# PowerBoard.net
KiCad netlist of a schematic drawn in EAGLE
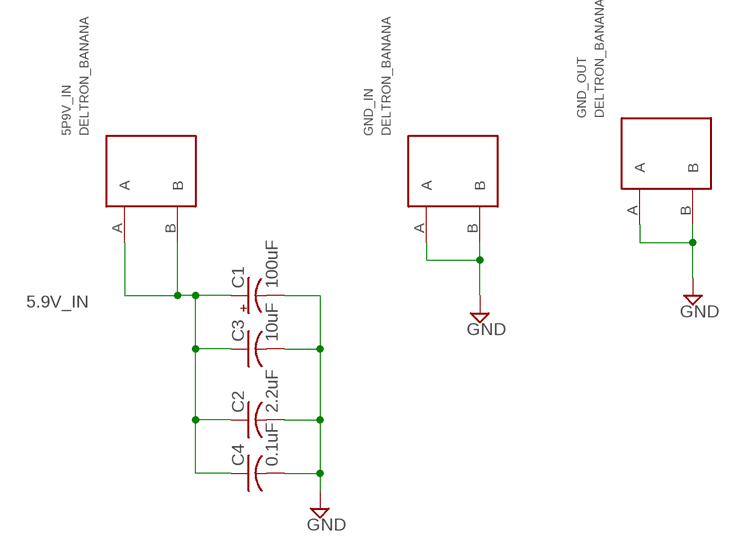
[diagram p0: schematic, sheet 1]
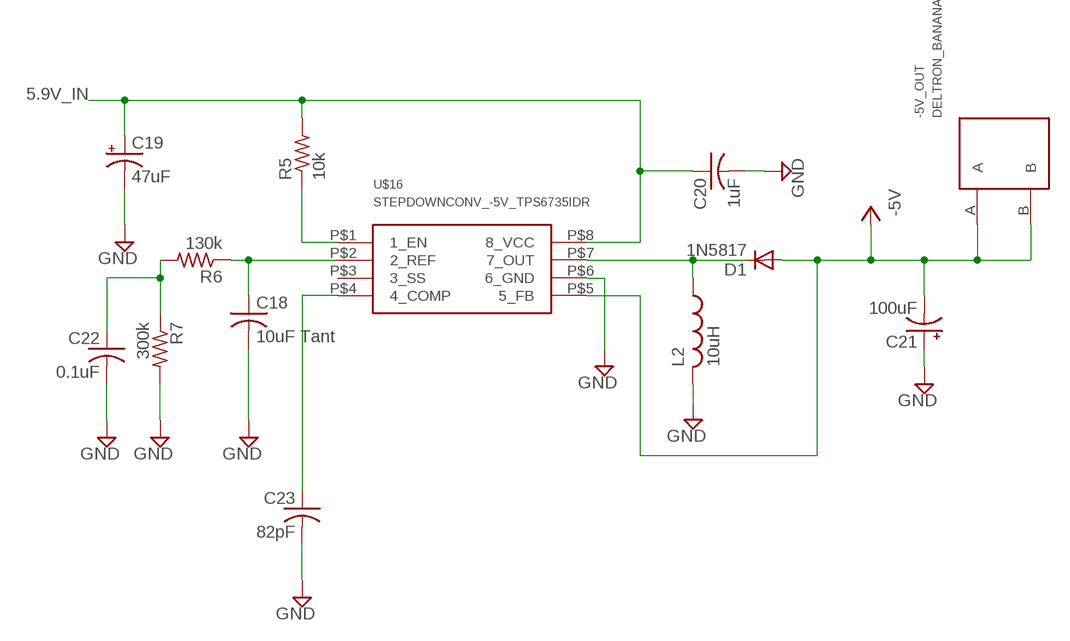
[diagram p1: schematic, sheet 2]
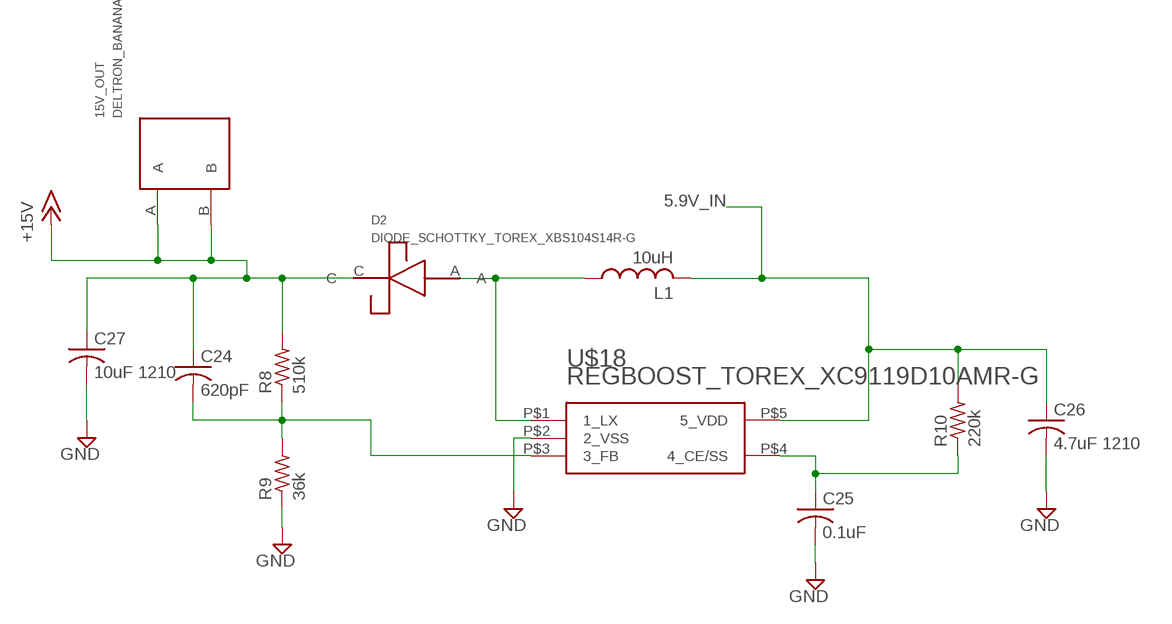
[diagram p2: schematic, sheet 3]
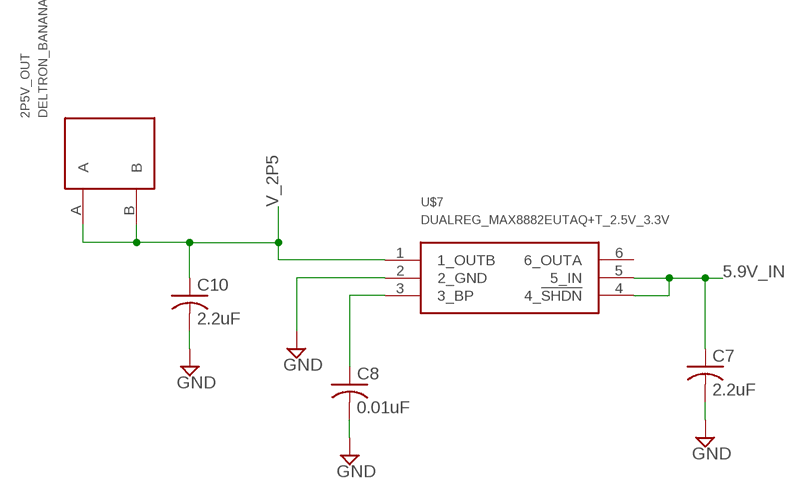
[diagram p3: schematic, sheet 4]

(export (version "E")
  (design (tool "Eeschema 10.0.6"))
  (components
    (comp (ref "15V_OUT")
      (value "DELTRON_BANANA")
      (footprint "eagle-import:DELTRON_BANANA")
      (libsource (lib "eagle-import") (part "DELTRON_BANANA"))
    )
    (comp (ref "C24")
      (value "620pF")
      (footprint "eagle-import:C0603")
      (libsource (lib "eagle-import") (part "C-USC0603"))
    )
    (comp (ref "C25")
      (value "0.1uF")
      (footprint "eagle-import:C0603")
      (libsource (lib "eagle-import") (part "C-USC0603"))
    )
    (comp (ref "C26")
      (value "4.7uF 1210")
      (footprint "eagle-import:C1210")
      (libsource (lib "eagle-import") (part "C-USC1210"))
    )
    (comp (ref "C27")
      (value "10uF 1210")
      (footprint "eagle-import:C1210")
      (libsource (lib "eagle-import") (part "C-USC1210"))
    )
    (comp (ref "D2")
      (value "DIODE_SCHOTTKY_TOREX_XBS104S14R-G")
      (footprint "eagle-import:SOD-123A")
      (libsource (lib "eagle-import") (part "DIODE_SCHOTTKY_TOREX_XBS104S14R-G"))
    )
    (comp (ref "L1")
      (value "10uH")
      (footprint "eagle-import:SUMIDA_INDUCTOR_CDRH4D18CNP-100PC")
      (libsource (lib "eagle-import") (part "SUMIDA_10UH_IND_CDRH4D18CNP-100PC"))
    )
    (comp (ref "R8")
      (value "510k")
      (footprint "eagle-import:R0603")
      (libsource (lib "eagle-import") (part "R-US_R0603"))
    )
    (comp (ref "R9")
      (value "36k")
      (footprint "eagle-import:R0603")
      (libsource (lib "eagle-import") (part "R-US_R0603"))
    )
    (comp (ref "R10")
      (value "220k")
      (footprint "eagle-import:R0603")
      (libsource (lib "eagle-import") (part "R-US_R0603"))
    )
    (comp (ref "U$18")
      (value "REGBOOST_TOREX_XC9119D10AMR-G")
      (footprint "eagle-import:SOT25-5")
      (libsource (lib "eagle-import") (part "REGBOOST_TOREX_XC9119D10AMR-G"))
    )
    (comp (ref "2P5V_OUT")
      (value "DELTRON_BANANA")
      (footprint "eagle-import:DELTRON_BANANA")
      (libsource (lib "eagle-import") (part "DELTRON_BANANA"))
    )
    (comp (ref "C7")
      (value "2.2uF")
      (footprint "eagle-import:C0603")
      (libsource (lib "eagle-import") (part "C-USC0603"))
    )
    (comp (ref "C8")
      (value "0.01uF")
      (footprint "eagle-import:C0603")
      (libsource (lib "eagle-import") (part "C-USC0603"))
    )
    (comp (ref "C10")
      (value "2.2uF")
      (footprint "eagle-import:C0603")
      (libsource (lib "eagle-import") (part "C-USC0603"))
    )
    (comp (ref "U$7")
      (value "DUALREG_MAX8882EUTAQ+T_2.5V_3.3V")
      (footprint "eagle-import:SOT23-6")
      (libsource (lib "eagle-import") (part "DUALREG_MAX8882EUTAQ+T_2.5V_3.3V"))
    )
    (comp (ref "-5V_OUT")
      (value "DELTRON_BANANA")
      (footprint "eagle-import:DELTRON_BANANA")
      (libsource (lib "eagle-import") (part "DELTRON_BANANA"))
    )
    (comp (ref "C18")
      (value "10uF Tant")
      (footprint "eagle-import:C1206")
      (libsource (lib "eagle-import") (part "C-USC1206"))
    )
    (comp (ref "C19")
      (value "47uF")
      (footprint "eagle-import:E5-10,5")
      (libsource (lib "eagle-import") (part "CPOL-USE5-10.5"))
    )
    (comp (ref "C20")
      (value "1uF")
      (footprint "eagle-import:C0603")
      (libsource (lib "eagle-import") (part "C-USC0603"))
    )
    (comp (ref "C21")
      (value "100uF")
      (footprint "eagle-import:E2,5-7")
      (libsource (lib "eagle-import") (part "CPOL-USE2.5-7"))
    )
    (comp (ref "C22")
      (value "0.1uF")
      (footprint "eagle-import:C0603")
      (libsource (lib "eagle-import") (part "C-USC0603"))
    )
    (comp (ref "C23")
      (value "82pF")
      (footprint "eagle-import:C0603")
      (libsource (lib "eagle-import") (part "C-USC0603"))
    )
    (comp (ref "D1")
      (value "1N5817")
      (footprint "eagle-import:DIODE-1N4148")
      (libsource (lib "eagle-import") (part "DIODE1N4148"))
    )
    (comp (ref "L2")
      (value "10uH")
      (footprint "eagle-import:COILCRAFT_POWERIND_DO1608C-103MLB")
      (libsource (lib "eagle-import") (part "COILCRAFT_10UHIND_DO1608C-103MLB"))
    )
    (comp (ref "R5")
      (value "10k")
      (footprint "eagle-import:R0603")
      (libsource (lib "eagle-import") (part "R-US_R0603"))
    )
    (comp (ref "R6")
      (value "130k")
      (footprint "eagle-import:R0603")
      (libsource (lib "eagle-import") (part "R-US_R0603"))
    )
    (comp (ref "R7")
      (value "300k")
      (footprint "eagle-import:R0603")
      (libsource (lib "eagle-import") (part "R-US_R0603"))
    )
    (comp (ref "U$16")
      (value "STEPDOWNCONV_-5V_TPS6735IDR")
      (footprint "eagle-import:SOIC8")
      (libsource (lib "eagle-import") (part "STEPDOWNCONV_-5V_TPS6735IDR"))
    )
    (comp (ref "5P9V_IN")
      (value "DELTRON_BANANA")
      (footprint "eagle-import:DELTRON_BANANA")
      (libsource (lib "eagle-import") (part "DELTRON_BANANA"))
    )
    (comp (ref "C1")
      (value "100uF")
      (footprint "eagle-import:CAP_POL_RADIAL_8MM_3P5MMPAD")
      (libsource (lib "eagle-import") (part "CAP_POL_DEV"))
    )
    (comp (ref "C2")
      (value "2.2uF")
      (footprint "eagle-import:C0603")
      (libsource (lib "eagle-import") (part "C-USC0603"))
    )
    (comp (ref "C3")
      (value "10uF")
      (footprint "eagle-import:C1206")
      (libsource (lib "eagle-import") (part "C-USC1206"))
    )
    (comp (ref "C4")
      (value "0.1uF")
      (footprint "eagle-import:C0603")
      (libsource (lib "eagle-import") (part "C-USC0603"))
    )
    (comp (ref "GND_IN")
      (value "DELTRON_BANANA")
      (footprint "eagle-import:DELTRON_BANANA")
      (libsource (lib "eagle-import") (part "DELTRON_BANANA"))
    )
    (comp (ref "GND_OUT")
      (value "DELTRON_BANANA")
      (footprint "eagle-import:DELTRON_BANANA")
      (libsource (lib "eagle-import") (part "DELTRON_BANANA"))
    )
  )
  (nets
    (net (code "1") (name "+15V") (class "Default")
      (node (ref "15V_OUT") (pin "A") (pinfunction "A_A") (pintype "bidirectional"))
      (node (ref "15V_OUT") (pin "B") (pinfunction "B_B") (pintype "bidirectional"))
      (node (ref "C24") (pin "1") (pinfunction "1_1") (pintype "passive"))
      (node (ref "C27") (pin "1") (pinfunction "1_1") (pintype "passive"))
      (node (ref "D2") (pin "C") (pinfunction "C_C") (pintype "bidirectional"))
      (node (ref "R8") (pin "2") (pinfunction "2_2") (pintype "passive"))
    )
    (net (code "2") (name "-5V") (class "Default")
      (node (ref "-5V_OUT") (pin "A") (pinfunction "A_A") (pintype "bidirectional"))
      (node (ref "-5V_OUT") (pin "B") (pinfunction "B_B") (pintype "bidirectional"))
      (node (ref "C21") (pin "-") (pinfunction "-_-") (pintype "passive"))
      (node (ref "D1") (pin "A") (pinfunction "A_A") (pintype "passive"))
      (node (ref "U$16") (pin "P$5") (pinfunction "5_FB_P$5") (pintype "bidirectional"))
    )
    (net (code "3") (name "5.9V_IN") (class "Default")
      (node (ref "5P9V_IN") (pin "A") (pinfunction "A_A") (pintype "bidirectional"))
      (node (ref "5P9V_IN") (pin "B") (pinfunction "B_B") (pintype "bidirectional"))
      (node (ref "C1") (pin "PIN+") (pinfunction "PIN+_PIN+") (pintype "passive"))
      (node (ref "C19") (pin "+") (pinfunction "+_+") (pintype "passive"))
      (node (ref "C2") (pin "1") (pinfunction "1_1") (pintype "passive"))
      (node (ref "C20") (pin "1") (pinfunction "1_1") (pintype "passive"))
      (node (ref "C26") (pin "1") (pinfunction "1_1") (pintype "passive"))
      (node (ref "C3") (pin "1") (pinfunction "1_1") (pintype "passive"))
      (node (ref "C4") (pin "1") (pinfunction "1_1") (pintype "passive"))
      (node (ref "C7") (pin "1") (pinfunction "1_1") (pintype "passive"))
      (node (ref "L1") (pin "P$2") (pinfunction "2_P$2") (pintype "passive"))
      (node (ref "R10") (pin "2") (pinfunction "2_2") (pintype "passive"))
      (node (ref "R5") (pin "2") (pinfunction "2_2") (pintype "passive"))
      (node (ref "U$16") (pin "P$8") (pinfunction "8_VCC_P$8") (pintype "bidirectional"))
      (node (ref "U$18") (pin "P$5") (pinfunction "5_VDD_P$5") (pintype "bidirectional"))
      (node (ref "U$7") (pin "4") (pinfunction "4_~{SHDN}_4") (pintype "bidirectional"))
      (node (ref "U$7") (pin "5") (pinfunction "5_IN_5") (pintype "bidirectional"))
    )
    (net (code "4") (name "GND") (class "Default")
      (node (ref "C1") (pin "PIN-") (pinfunction "PIN-_PIN-") (pintype "passive"))
      (node (ref "C10") (pin "2") (pinfunction "2_2") (pintype "passive"))
      (node (ref "C18") (pin "2") (pinfunction "2_2") (pintype "passive"))
      (node (ref "C19") (pin "-") (pinfunction "-_-") (pintype "passive"))
      (node (ref "C2") (pin "2") (pinfunction "2_2") (pintype "passive"))
      (node (ref "C20") (pin "2") (pinfunction "2_2") (pintype "passive"))
      (node (ref "C21") (pin "+") (pinfunction "+_+") (pintype "passive"))
      (node (ref "C22") (pin "2") (pinfunction "2_2") (pintype "passive"))
      (node (ref "C23") (pin "2") (pinfunction "2_2") (pintype "passive"))
      (node (ref "C25") (pin "2") (pinfunction "2_2") (pintype "passive"))
      (node (ref "C26") (pin "2") (pinfunction "2_2") (pintype "passive"))
      (node (ref "C27") (pin "2") (pinfunction "2_2") (pintype "passive"))
      (node (ref "C3") (pin "2") (pinfunction "2_2") (pintype "passive"))
      (node (ref "C4") (pin "2") (pinfunction "2_2") (pintype "passive"))
      (node (ref "C7") (pin "2") (pinfunction "2_2") (pintype "passive"))
      (node (ref "C8") (pin "2") (pinfunction "2_2") (pintype "passive"))
      (node (ref "GND_IN") (pin "A") (pinfunction "A_A") (pintype "bidirectional"))
      (node (ref "GND_IN") (pin "B") (pinfunction "B_B") (pintype "bidirectional"))
      (node (ref "GND_OUT") (pin "A") (pinfunction "A_A") (pintype "bidirectional"))
      (node (ref "GND_OUT") (pin "B") (pinfunction "B_B") (pintype "bidirectional"))
      (node (ref "L2") (pin "P$2") (pinfunction "2_P$2") (pintype "passive"))
      (node (ref "R7") (pin "2") (pinfunction "2_2") (pintype "passive"))
      (node (ref "R9") (pin "1") (pinfunction "1_1") (pintype "passive"))
      (node (ref "U$16") (pin "P$6") (pinfunction "6_GND_P$6") (pintype "bidirectional"))
      (node (ref "U$18") (pin "P$2") (pinfunction "2_VSS_P$2") (pintype "bidirectional"))
      (node (ref "U$7") (pin "2") (pinfunction "2_GND_2") (pintype "bidirectional"))
    )
    (net (code "5") (name "Net-(C22-Pad1)") (class "Default")
      (node (ref "C22") (pin "1") (pinfunction "1_1") (pintype "passive"))
      (node (ref "R6") (pin "2") (pinfunction "2_2") (pintype "passive"))
      (node (ref "R7") (pin "1") (pinfunction "1_1") (pintype "passive"))
    )
    (net (code "6") (name "Net-(L1-1)") (class "Default")
      (node (ref "D2") (pin "A") (pinfunction "A_A") (pintype "bidirectional"))
      (node (ref "L1") (pin "P$1") (pinfunction "1_P$1") (pintype "passive"))
      (node (ref "U$18") (pin "P$1") (pinfunction "1_LX_P$1") (pintype "bidirectional"))
    )
    (net (code "7") (name "Net-(L2-1)") (class "Default")
      (node (ref "D1") (pin "C") (pinfunction "C_C") (pintype "passive"))
      (node (ref "L2") (pin "P$1") (pinfunction "1_P$1") (pintype "passive"))
      (node (ref "U$16") (pin "P$7") (pinfunction "7_OUT_P$7") (pintype "bidirectional"))
    )
    (net (code "8") (name "Net-(U$7-3_BP)") (class "Default")
      (node (ref "C8") (pin "1") (pinfunction "1_1") (pintype "passive"))
      (node (ref "U$7") (pin "3") (pinfunction "3_BP_3") (pintype "bidirectional"))
    )
    (net (code "9") (name "Net-(U$16-1_EN)") (class "Default")
      (node (ref "R5") (pin "1") (pinfunction "1_1") (pintype "passive"))
      (node (ref "U$16") (pin "P$1") (pinfunction "1_EN_P$1") (pintype "bidirectional"))
    )
    (net (code "10") (name "Net-(U$16-2_REF)") (class "Default")
      (node (ref "C18") (pin "1") (pinfunction "1_1") (pintype "passive"))
      (node (ref "R6") (pin "1") (pinfunction "1_1") (pintype "passive"))
      (node (ref "U$16") (pin "P$2") (pinfunction "2_REF_P$2") (pintype "bidirectional"))
    )
    (net (code "11") (name "Net-(U$16-4_COMP)") (class "Default")
      (node (ref "C23") (pin "1") (pinfunction "1_1") (pintype "passive"))
      (node (ref "U$16") (pin "P$4") (pinfunction "4_COMP_P$4") (pintype "bidirectional"))
    )
    (net (code "12") (name "Net-(U$18-3_FB)") (class "Default")
      (node (ref "C24") (pin "2") (pinfunction "2_2") (pintype "passive"))
      (node (ref "R8") (pin "1") (pinfunction "1_1") (pintype "passive"))
      (node (ref "R9") (pin "2") (pinfunction "2_2") (pintype "passive"))
      (node (ref "U$18") (pin "P$3") (pinfunction "3_FB_P$3") (pintype "bidirectional"))
    )
    (net (code "13") (name "Net-(U$18-4_CE{slash}SS)") (class "Default")
      (node (ref "C25") (pin "1") (pinfunction "1_1") (pintype "passive"))
      (node (ref "R10") (pin "1") (pinfunction "1_1") (pintype "passive"))
      (node (ref "U$18") (pin "P$4") (pinfunction "4_CE/SS_P$4") (pintype "bidirectional"))
    )
    (net (code "14") (name "V_2P5") (class "Default")
      (node (ref "2P5V_OUT") (pin "A") (pinfunction "A_A") (pintype "bidirectional"))
      (node (ref "2P5V_OUT") (pin "B") (pinfunction "B_B") (pintype "bidirectional"))
      (node (ref "C10") (pin "1") (pinfunction "1_1") (pintype "passive"))
      (node (ref "U$7") (pin "1") (pinfunction "1_OUTB_1") (pintype "bidirectional"))
    )
    (net (code "15") (name "unconnected-(U$7-6_OUTA-Pad6)") (class "Default")
      (node (ref "U$7") (pin "6") (pinfunction "6_OUTA_6") (pintype "bidirectional"))
    )
    (net (code "16") (name "unconnected-(U$16-3_SS-PadP$3)") (class "Default")
      (node (ref "U$16") (pin "P$3") (pinfunction "3_SS_P$3") (pintype "bidirectional"))
    )
  )
)
